# design.net
KiCad netlist of a schematic drawn in Altium Designer
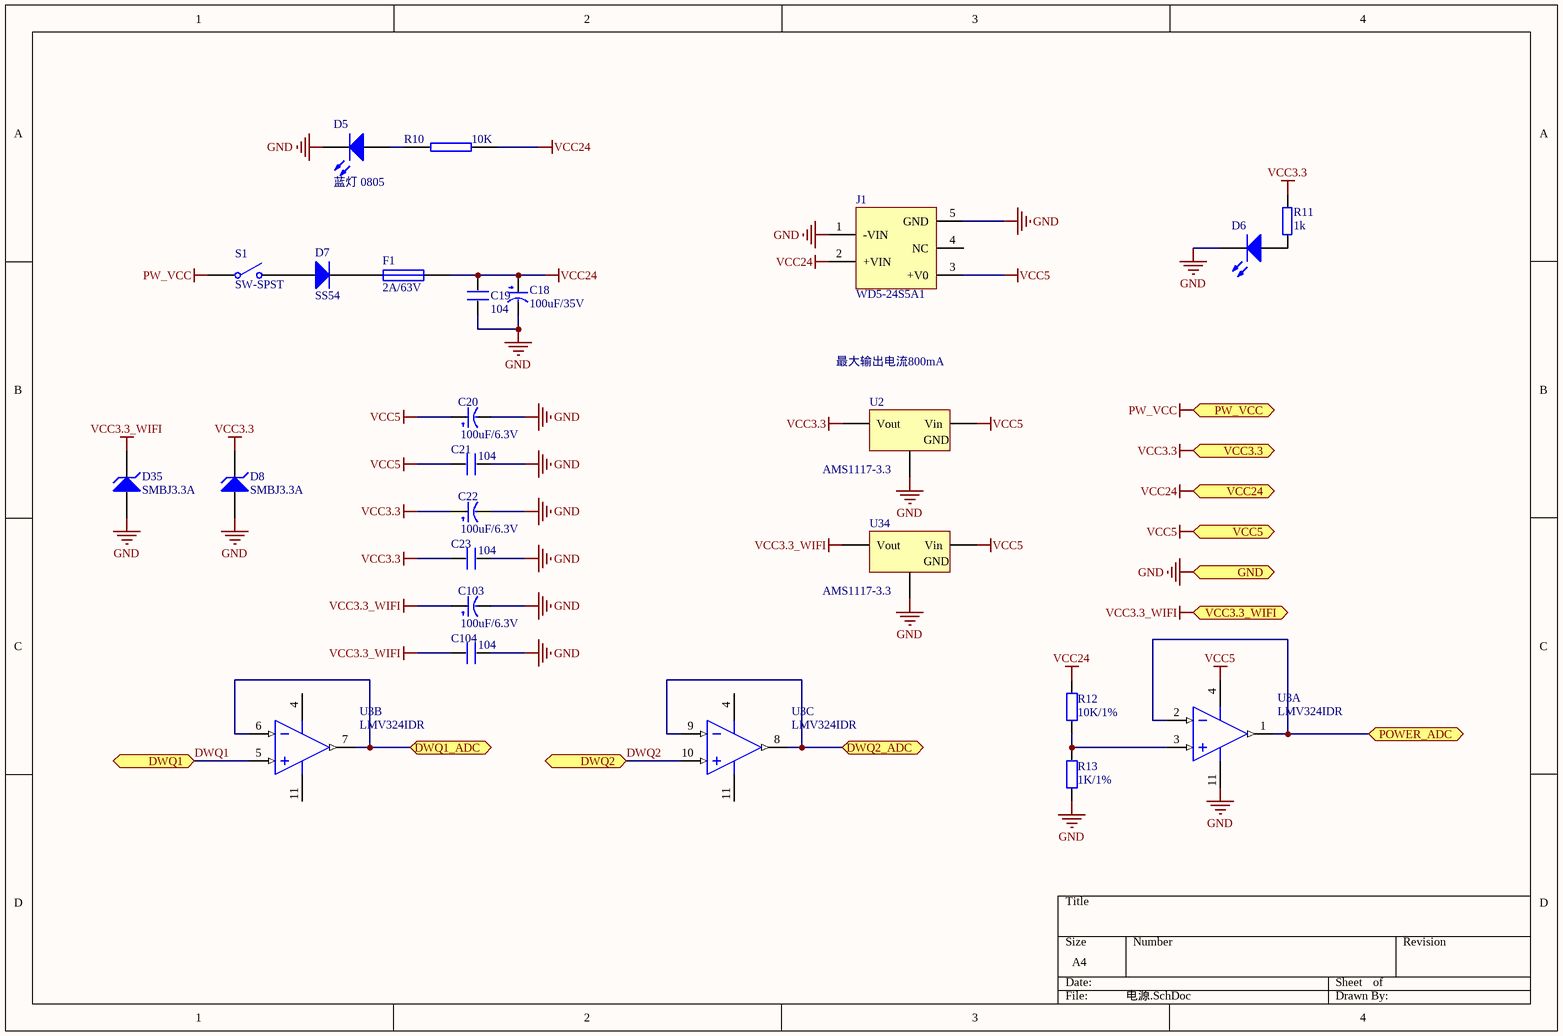
[diagram p0: 电源.SchDoc]

(export (version "E")
  (design (tool "Eeschema 10.0.6"))
  (components
    (comp (ref "C18")
      (value "100uF/35V")
      (footprint "CC6.56.5")
      (libsource (lib "WarShip V3_SCH") (part "CAP"))
    )
    (comp (ref "C19") (value "104") (footprint "0805_C") (libsource (lib "WarShip V3_SCH") (part "C")))
    (comp (ref "C20")
      (value "100uF/6.3V")
      (footprint "CASE-B_3528")
      (libsource (lib "WarShip V3_SCH") (part "CAP"))
    )
    (comp (ref "C21") (value "104") (footprint "0805_C") (libsource (lib "WarShip V3_SCH") (part "C")))
    (comp (ref "C22")
      (value "100uF/6.3V")
      (footprint "CASE-B_3528")
      (libsource (lib "WarShip V3_SCH") (part "CAP"))
    )
    (comp (ref "C23") (value "104") (footprint "0805_C") (libsource (lib "WarShip V3_SCH") (part "C")))
    (comp (ref "C103")
      (value "100uF/6.3V")
      (footprint "CASE-B_3528")
      (libsource (lib "WarShip V3_SCH") (part "CAP"))
    )
    (comp (ref "C104") (value "104") (footprint "0805_C") (libsource (lib "WarShip V3_SCH") (part "C")))
    (comp (ref "D5")
      (value "蓝灯 0805")
      (footprint "0805_LED_S1")
      (description "发光二极管")
      (libsource (lib "Miscellaneous Devices LC - 副本") (part "0805 蓝灯"))
    )
    (comp (ref "D6")
      (value "蓝灯 0805")
      (footprint "LC-0805_LED_S1")
      (description "Typical INFRARED GaAs LED")
      (fields (field (name "PUBLISHER") "Altium Limited"))
      (libsource (lib "继电器板_1") (part "LED0"))
    )
    (comp (ref "D7")
      (value "SS54")
      (footprint "SMA(DO-214AC)_S1")
      (description "二极管")
      (libsource (lib "Miscellaneous Devices LC") (part "SMA(DO-214AC) SS54"))
    )
    (comp (ref "D8")
      (value "SMBJ3.3A")
      (footprint "SMB(DO-214AA)_S1")
      (description "Zener Diode")
      (fields (field (name "PUBLISHER") "Altium Limited"))
      (libsource (lib "Miscellaneous Devices") (part "D Zener"))
    )
    (comp (ref "D35")
      (value "SMBJ3.3A")
      (footprint "SMB(DO-214AA)_S1")
      (description "Zener Diode")
      (fields (field (name "PUBLISHER") "Altium Limited"))
      (libsource (lib "Miscellaneous Devices") (part "D Zener"))
    )
    (comp (ref "F1")
      (value "2A/63V")
      (footprint "1206")
      (description "Fuse")
      (fields (field (name "PUBLISHER") "Altium Limited"))
      (libsource (lib "Miscellaneous Devices") (part "Fuse 1"))
    )
    (comp (ref "J1")
      (value "WD5-24S5A1")
      (footprint "WD5-24S3V3")
      (libsource (lib "*") (part "WD5-24S3V3A1"))
    )
    (comp (ref "R10") (value "10K") (footprint "0603_R") (libsource (lib "*") (part "RES2")))
    (comp (ref "R11")
      (value "1k")
      (footprint "0805_R")
      (libsource (lib "Explorer STM32F407封装库") (part "R_2"))
    )
    (comp (ref "R12")
      (value "10K/1%")
      (footprint "0805_R")
      (description "Resistor")
      (fields (field (name "PUBLISHER") "Altium Limited"))
      (libsource (lib "Miscellaneous Devices") (part "Res2"))
    )
    (comp (ref "R13")
      (value "1K/1%")
      (footprint "0805_R")
      (description "Resistor")
      (fields (field (name "PUBLISHER") "Altium Limited"))
      (libsource (lib "Miscellaneous Devices") (part "Res2"))
    )
    (comp (ref "S1")
      (value "SW-SPST")
      (footprint "SPST-2")
      (description "Single-Pole, Single-Throw Switch")
      (fields (field (name "PUBLISHER") "Altium Limited"))
      (libsource (lib "Miscellaneous Devices") (part "SW-SPST"))
    )
    (comp (ref "U2")
      (value "AMS1117-3.3")
      (footprint "SOT-223")
      (description "低压差线性稳压(LDO)")
      (libsource (lib "Miscellaneous Devices LC") (part "SOT-223 AMS1117-3.3"))
    )
    (comp (ref "U3")
      (value "LMV324IDR")
      (footprint "SOIC-14_150mil")
      (description "运放")
      (libsource (lib "Miscellaneous Devices LC") (part "LMV324IDR"))
    )
    (comp (ref "U34")
      (value "AMS1117-3.3")
      (footprint "SOT-223")
      (description "低压差线性稳压(LDO)")
      (libsource (lib "Miscellaneous Devices LC") (part "SOT-223 AMS1117-3.3"))
    )
  )
  (nets
    (net (code "1") (name "/DWQ1") (class "Default")
      (node (ref "U3") (pin "5") (pinfunction "INB+_5") (pintype "input"))
    )
    (net (code "2") (name "/DWQ1_ADC") (class "Default")
      (node (ref "U3") (pin "6") (pinfunction "INB-_6") (pintype "input"))
      (node (ref "U3") (pin "7") (pinfunction "OUTB_7") (pintype "output"))
    )
    (net (code "3") (name "/DWQ2") (class "Default")
      (node (ref "U3") (pin "10") (pinfunction "INC+_10") (pintype "input"))
    )
    (net (code "4") (name "/DWQ2_ADC") (class "Default")
      (node (ref "U3") (pin "8") (pinfunction "OUTC_8") (pintype "output"))
      (node (ref "U3") (pin "9") (pinfunction "INC-_9") (pintype "input"))
    )
    (net (code "5") (name "/POWER_ADC") (class "Default")
      (node (ref "U3") (pin "1") (pinfunction "OUTA_1") (pintype "output"))
      (node (ref "U3") (pin "2") (pinfunction "INA-_2") (pintype "input"))
    )
    (net (code "6") (name "GND") (class "Default")
      (node (ref "C103") (pin "2") (pinfunction "GND_2") (pintype "passive"))
      (node (ref "C104") (pin "1") (pintype "passive"))
      (node (ref "C18") (pin "2") (pinfunction "GND_2") (pintype "passive"))
      (node (ref "C19") (pin "2") (pintype "passive"))
      (node (ref "C20") (pin "2") (pinfunction "GND_2") (pintype "passive"))
      (node (ref "C21") (pin "1") (pintype "passive"))
      (node (ref "C22") (pin "2") (pinfunction "GND_2") (pintype "passive"))
      (node (ref "C23") (pin "1") (pintype "passive"))
      (node (ref "D35") (pin "1") (pinfunction "A_1") (pintype "passive"))
      (node (ref "D5") (pin "K") (pinfunction "K_K") (pintype "passive"))
      (node (ref "D6") (pin "K") (pinfunction "K_K") (pintype "passive"))
      (node (ref "D8") (pin "1") (pinfunction "A_1") (pintype "passive"))
      (node (ref "J1") (pin "1") (pinfunction "-VIN_1") (pintype "passive"))
      (node (ref "J1") (pin "5") (pinfunction "GND_5") (pintype "passive"))
      (node (ref "R13") (pin "1") (pinfunction "1_1") (pintype "passive"))
      (node (ref "U2") (pin "1") (pinfunction "GND_1") (pintype "passive"))
      (node (ref "U3") (pin "11") (pinfunction "V-_11") (pintype "power_in"))
      (node (ref "U34") (pin "1") (pinfunction "GND_1") (pintype "passive"))
    )
    (net (code "7") (name "Net-(D5-PadA)") (class "Default")
      (node (ref "D5") (pin "A") (pinfunction "A_A") (pintype "passive"))
      (node (ref "R10") (pin "2") (pinfunction "2_2") (pintype "passive"))
    )
    (net (code "8") (name "Net-(D6-PadA)") (class "Default")
      (node (ref "D6") (pin "A") (pinfunction "A_A") (pintype "passive"))
      (node (ref "R11") (pin "2") (pintype "passive"))
    )
    (net (code "9") (name "Net-(D7-A)") (class "Default")
      (node (ref "D7") (pin "1") (pinfunction "A_1") (pintype "passive"))
      (node (ref "S1") (pin "2") (pinfunction "NO_2") (pintype "passive"))
    )
    (net (code "10") (name "Net-(D7-K)") (class "Default")
      (node (ref "D7") (pin "2") (pinfunction "K_2") (pintype "passive"))
      (node (ref "F1") (pin "1") (pinfunction "1_1") (pintype "passive"))
    )
    (net (code "11") (name "Net-(U3A-INA+)") (class "Default")
      (node (ref "R12") (pin "1") (pinfunction "1_1") (pintype "passive"))
      (node (ref "R13") (pin "2") (pinfunction "2_2") (pintype "passive"))
      (node (ref "U3") (pin "3") (pinfunction "INA+_3") (pintype "input"))
    )
    (net (code "12") (name "PW_VCC") (class "Default")
      (node (ref "S1") (pin "1") (pinfunction "COMMON_1") (pintype "passive"))
    )
    (net (code "13") (name "VCC3.3") (class "Default")
      (node (ref "C22") (pin "1") (pinfunction "VCC_1") (pintype "passive"))
      (node (ref "C23") (pin "2") (pintype "passive"))
      (node (ref "D8") (pin "2") (pinfunction "K_2") (pintype "passive"))
      (node (ref "R11") (pin "1") (pintype "passive"))
      (node (ref "U2") (pin "2") (pinfunction "Vout_2") (pintype "passive"))
    )
    (net (code "14") (name "VCC3.3_WIFI") (class "Default")
      (node (ref "C103") (pin "1") (pinfunction "VCC_1") (pintype "passive"))
      (node (ref "C104") (pin "2") (pintype "passive"))
      (node (ref "D35") (pin "2") (pinfunction "K_2") (pintype "passive"))
      (node (ref "U34") (pin "2") (pinfunction "Vout_2") (pintype "passive"))
    )
    (net (code "15") (name "VCC5") (class "Default")
      (node (ref "C20") (pin "1") (pinfunction "VCC_1") (pintype "passive"))
      (node (ref "C21") (pin "2") (pintype "passive"))
      (node (ref "J1") (pin "3") (pinfunction "+V0_3") (pintype "passive"))
      (node (ref "U2") (pin "3") (pinfunction "Vin_3") (pintype "passive"))
      (node (ref "U3") (pin "4") (pinfunction "V+_4") (pintype "power_in"))
      (node (ref "U34") (pin "3") (pinfunction "Vin_3") (pintype "passive"))
    )
    (net (code "16") (name "VCC24") (class "Default")
      (node (ref "C18") (pin "1") (pinfunction "VCC_1") (pintype "passive"))
      (node (ref "C19") (pin "1") (pintype "passive"))
      (node (ref "F1") (pin "2") (pinfunction "2_2") (pintype "passive"))
      (node (ref "J1") (pin "2") (pinfunction "+VIN_2") (pintype "passive"))
      (node (ref "R10") (pin "1") (pinfunction "1_1") (pintype "passive"))
      (node (ref "R12") (pin "2") (pinfunction "2_2") (pintype "passive"))
    )
    (net (code "17") (name "unconnected-(J1-NC-Pad4)") (class "Default")
      (node (ref "J1") (pin "4") (pinfunction "NC_4") (pintype "passive"))
    )
    (net (code "18") (name "unconnected-(U3B-V+-Pad4)") (class "Default")
      (node (ref "U3") (pin "4") (pinfunction "V+_4") (pintype "power_in"))
    )
    (net (code "19") (name "unconnected-(U3B-V--Pad11)") (class "Default")
      (node (ref "U3") (pin "11") (pinfunction "V-_11") (pintype "power_in"))
    )
    (net (code "20") (name "unconnected-(U3C-V+-Pad4)") (class "Default")
      (node (ref "U3") (pin "4") (pinfunction "V+_4") (pintype "power_in"))
    )
    (net (code "21") (name "unconnected-(U3C-V--Pad11)") (class "Default")
      (node (ref "U3") (pin "11") (pinfunction "V-_11") (pintype "power_in"))
    )
  )
)
